# MMProtoShield.net
KiCad netlist of a schematic drawn in EAGLE
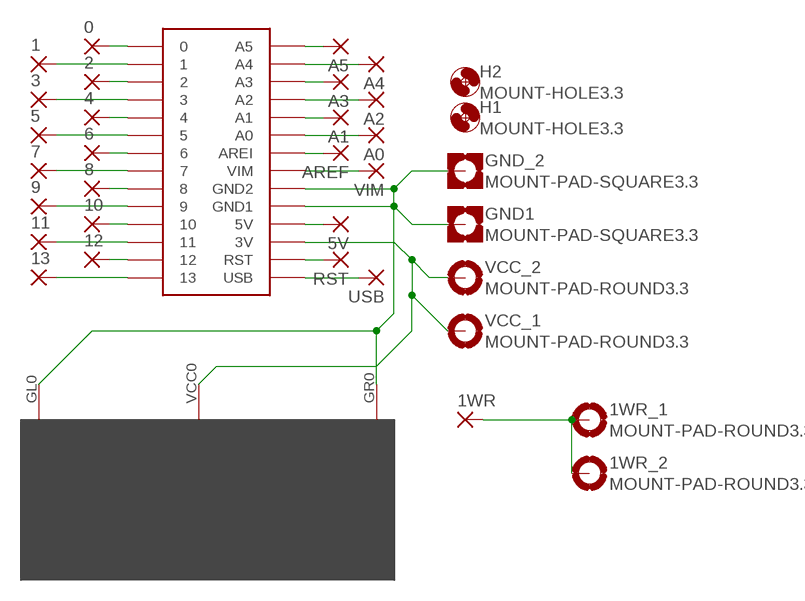
[diagram p0: schematic, sheet 1]

(export (version "E")
  (design (tool "Eeschema 10.0.6"))
  (components
    (comp (ref "0")
      (value "1,6/0,9")
      (footprint "eagle-import:1,6_0,9")
      (libsource (lib "eagle-import") (part "1,6/0,9"))
    )
    (comp (ref "1")
      (value "1,6/0,9")
      (footprint "eagle-import:1,6_0,9")
      (libsource (lib "eagle-import") (part "1,6/0,9"))
    )
    (comp (ref "1WR")
      (value "1,6/0,9")
      (footprint "eagle-import:1,6_0,9")
      (libsource (lib "eagle-import") (part "1,6/0,9"))
    )
    (comp (ref "1WR_1")
      (value "MOUNT-PAD-ROUND3.3")
      (footprint "eagle-import:3,3-PAD")
      (libsource (lib "eagle-import") (part "MOUNT-PAD-ROUND3.3"))
    )
    (comp (ref "1WR_2")
      (value "MOUNT-PAD-ROUND3.3")
      (footprint "eagle-import:3,3-PAD")
      (libsource (lib "eagle-import") (part "MOUNT-PAD-ROUND3.3"))
    )
    (comp (ref "2")
      (value "1,6/0,9")
      (footprint "eagle-import:1,6_0,9")
      (libsource (lib "eagle-import") (part "1,6/0,9"))
    )
    (comp (ref "3")
      (value "1,6/0,9")
      (footprint "eagle-import:1,6_0,9")
      (libsource (lib "eagle-import") (part "1,6/0,9"))
    )
    (comp (ref "4")
      (value "1,6/0,9")
      (footprint "eagle-import:1,6_0,9")
      (libsource (lib "eagle-import") (part "1,6/0,9"))
    )
    (comp (ref "5")
      (value "1,6/0,9")
      (footprint "eagle-import:1,6_0,9")
      (libsource (lib "eagle-import") (part "1,6/0,9"))
    )
    (comp (ref "5V")
      (value "1,6/0,9")
      (footprint "eagle-import:1,6_0,9")
      (libsource (lib "eagle-import") (part "1,6/0,9"))
    )
    (comp (ref "6")
      (value "1,6/0,9")
      (footprint "eagle-import:1,6_0,9")
      (libsource (lib "eagle-import") (part "1,6/0,9"))
    )
    (comp (ref "7")
      (value "1,6/0,9")
      (footprint "eagle-import:1,6_0,9")
      (libsource (lib "eagle-import") (part "1,6/0,9"))
    )
    (comp (ref "8")
      (value "1,6/0,9")
      (footprint "eagle-import:1,6_0,9")
      (libsource (lib "eagle-import") (part "1,6/0,9"))
    )
    (comp (ref "9")
      (value "1,6/0,9")
      (footprint "eagle-import:1,6_0,9")
      (libsource (lib "eagle-import") (part "1,6/0,9"))
    )
    (comp (ref "10")
      (value "1,6/0,9")
      (footprint "eagle-import:1,6_0,9")
      (libsource (lib "eagle-import") (part "1,6/0,9"))
    )
    (comp (ref "11")
      (value "1,6/0,9")
      (footprint "eagle-import:1,6_0,9")
      (libsource (lib "eagle-import") (part "1,6/0,9"))
    )
    (comp (ref "12")
      (value "1,6/0,9")
      (footprint "eagle-import:1,6_0,9")
      (libsource (lib "eagle-import") (part "1,6/0,9"))
    )
    (comp (ref "13")
      (value "1,6/0,9")
      (footprint "eagle-import:1,6_0,9")
      (libsource (lib "eagle-import") (part "1,6/0,9"))
    )
    (comp (ref "A0")
      (value "1,6/0,9")
      (footprint "eagle-import:1,6_0,9")
      (libsource (lib "eagle-import") (part "1,6/0,9"))
    )
    (comp (ref "A1")
      (value "1,6/0,9")
      (footprint "eagle-import:1,6_0,9")
      (libsource (lib "eagle-import") (part "1,6/0,9"))
    )
    (comp (ref "A2")
      (value "1,6/0,9")
      (footprint "eagle-import:1,6_0,9")
      (libsource (lib "eagle-import") (part "1,6/0,9"))
    )
    (comp (ref "A3")
      (value "1,6/0,9")
      (footprint "eagle-import:1,6_0,9")
      (libsource (lib "eagle-import") (part "1,6/0,9"))
    )
    (comp (ref "A4")
      (value "1,6/0,9")
      (footprint "eagle-import:1,6_0,9")
      (libsource (lib "eagle-import") (part "1,6/0,9"))
    )
    (comp (ref "A5")
      (value "1,6/0,9")
      (footprint "eagle-import:1,6_0,9")
      (libsource (lib "eagle-import") (part "1,6/0,9"))
    )
    (comp (ref "AREF")
      (value "1,6/0,9")
      (footprint "eagle-import:1,6_0,9")
      (libsource (lib "eagle-import") (part "1,6/0,9"))
    )
    (comp (ref "GND1")
      (value "MOUNT-PAD-SQUARE3.3")
      (footprint "eagle-import:3,3-PAD-SQUARE")
      (libsource (lib "eagle-import") (part "MOUNT-PAD-SQUARE3.3"))
    )
    (comp (ref "GND_2")
      (value "MOUNT-PAD-SQUARE3.3")
      (footprint "eagle-import:3,3-PAD-SQUARE")
      (libsource (lib "eagle-import") (part "MOUNT-PAD-SQUARE3.3"))
    )
    (comp (ref "H1")
      (value "MOUNT-HOLE3.3")
      (footprint "eagle-import:3,3")
      (libsource (lib "eagle-import") (part "MOUNT-HOLE3.3"))
    )
    (comp (ref "H2")
      (value "MOUNT-HOLE3.3")
      (footprint "eagle-import:3,3")
      (libsource (lib "eagle-import") (part "MOUNT-HOLE3.3"))
    )
    (comp (ref "RST")
      (value "1,6/0,9")
      (footprint "eagle-import:1,6_0,9")
      (libsource (lib "eagle-import") (part "1,6/0,9"))
    )
    (comp (ref "U$1")
      (value "METRO_MINI_FOOTPRINT")
      (footprint "eagle-import:METRO_MINI_FOOTPRINT")
      (libsource (lib "eagle-import") (part "METRO_MINI_FOOTPRINT"))
    )
    (comp (ref "U$2")
      (value "PROTOAREA")
      (footprint "eagle-import:PROTOAREA")
      (libsource (lib "eagle-import") (part "PROTOAREA"))
    )
    (comp (ref "USB")
      (value "1,6/0,9")
      (footprint "eagle-import:1,6_0,9")
      (libsource (lib "eagle-import") (part "1,6/0,9"))
    )
    (comp (ref "VCC_1")
      (value "MOUNT-PAD-ROUND3.3")
      (footprint "eagle-import:3,3-PAD")
      (libsource (lib "eagle-import") (part "MOUNT-PAD-ROUND3.3"))
    )
    (comp (ref "VCC_2")
      (value "MOUNT-PAD-ROUND3.3")
      (footprint "eagle-import:3,3-PAD")
      (libsource (lib "eagle-import") (part "MOUNT-PAD-ROUND3.3"))
    )
    (comp (ref "VIM")
      (value "1,6/0,9")
      (footprint "eagle-import:1,6_0,9")
      (libsource (lib "eagle-import") (part "1,6/0,9"))
    )
  )
  (nets
    (net (code "1") (name "Net-(0-P)") (class "Default")
      (node (ref "0") (pin "1") (pinfunction "P_1") (pintype "passive"))
      (node (ref "U$1") (pin "0") (pinfunction "0_0") (pintype "bidirectional"))
    )
    (net (code "2") (name "Net-(1-P)") (class "Default")
      (node (ref "1") (pin "1") (pinfunction "P_1") (pintype "passive"))
      (node (ref "U$1") (pin "1") (pinfunction "1_1") (pintype "bidirectional"))
    )
    (net (code "3") (name "Net-(1WR-P)") (class "Default")
      (node (ref "1WR") (pin "1") (pinfunction "P_1") (pintype "passive"))
      (node (ref "1WR_1") (pin "B3,3") (pinfunction "MOUNT_B3,3") (pintype "passive"))
      (node (ref "1WR_2") (pin "B3,3") (pinfunction "MOUNT_B3,3") (pintype "passive"))
    )
    (net (code "4") (name "Net-(2-P)") (class "Default")
      (node (ref "2") (pin "1") (pinfunction "P_1") (pintype "passive"))
      (node (ref "U$1") (pin "2") (pinfunction "2_2") (pintype "bidirectional"))
    )
    (net (code "5") (name "Net-(3-P)") (class "Default")
      (node (ref "3") (pin "1") (pinfunction "P_1") (pintype "passive"))
      (node (ref "U$1") (pin "3") (pinfunction "3_3") (pintype "bidirectional"))
    )
    (net (code "6") (name "Net-(4-P)") (class "Default")
      (node (ref "4") (pin "1") (pinfunction "P_1") (pintype "passive"))
      (node (ref "U$1") (pin "4") (pinfunction "4_4") (pintype "bidirectional"))
    )
    (net (code "7") (name "Net-(5-P)") (class "Default")
      (node (ref "5") (pin "1") (pinfunction "P_1") (pintype "passive"))
      (node (ref "U$1") (pin "5") (pinfunction "5_5") (pintype "bidirectional"))
    )
    (net (code "8") (name "Net-(5V-P)") (class "Default")
      (node (ref "5V") (pin "1") (pinfunction "P_1") (pintype "passive"))
      (node (ref "U$1") (pin "5V") (pinfunction "5V_5V") (pintype "bidirectional"))
    )
    (net (code "9") (name "Net-(6-P)") (class "Default")
      (node (ref "6") (pin "1") (pinfunction "P_1") (pintype "passive"))
      (node (ref "U$1") (pin "6") (pinfunction "6_6") (pintype "bidirectional"))
    )
    (net (code "10") (name "Net-(7-P)") (class "Default")
      (node (ref "7") (pin "1") (pinfunction "P_1") (pintype "passive"))
      (node (ref "U$1") (pin "7") (pinfunction "7_7") (pintype "bidirectional"))
    )
    (net (code "11") (name "Net-(8-P)") (class "Default")
      (node (ref "8") (pin "1") (pinfunction "P_1") (pintype "passive"))
      (node (ref "U$1") (pin "8") (pinfunction "8_8") (pintype "bidirectional"))
    )
    (net (code "12") (name "Net-(9-P)") (class "Default")
      (node (ref "9") (pin "1") (pinfunction "P_1") (pintype "passive"))
      (node (ref "U$1") (pin "9") (pinfunction "9_9") (pintype "bidirectional"))
    )
    (net (code "13") (name "Net-(10-P)") (class "Default")
      (node (ref "10") (pin "1") (pinfunction "P_1") (pintype "passive"))
      (node (ref "U$1") (pin "10") (pinfunction "10_10") (pintype "bidirectional"))
    )
    (net (code "14") (name "Net-(11-P)") (class "Default")
      (node (ref "11") (pin "1") (pinfunction "P_1") (pintype "passive"))
      (node (ref "U$1") (pin "11") (pinfunction "11_11") (pintype "bidirectional"))
    )
    (net (code "15") (name "Net-(12-P)") (class "Default")
      (node (ref "12") (pin "1") (pinfunction "P_1") (pintype "passive"))
      (node (ref "U$1") (pin "12") (pinfunction "12_12") (pintype "bidirectional"))
    )
    (net (code "16") (name "Net-(13-P)") (class "Default")
      (node (ref "13") (pin "1") (pinfunction "P_1") (pintype "passive"))
      (node (ref "U$1") (pin "13") (pinfunction "13_13") (pintype "bidirectional"))
    )
    (net (code "17") (name "Net-(A0-P)") (class "Default")
      (node (ref "A0") (pin "1") (pinfunction "P_1") (pintype "passive"))
      (node (ref "U$1") (pin "A0") (pinfunction "A0_A0") (pintype "bidirectional"))
    )
    (net (code "18") (name "Net-(A1-P)") (class "Default")
      (node (ref "A1") (pin "1") (pinfunction "P_1") (pintype "passive"))
      (node (ref "U$1") (pin "A1") (pinfunction "A1_A1") (pintype "bidirectional"))
    )
    (net (code "19") (name "Net-(A2-P)") (class "Default")
      (node (ref "A2") (pin "1") (pinfunction "P_1") (pintype "passive"))
      (node (ref "U$1") (pin "A2") (pinfunction "A2_A2") (pintype "bidirectional"))
    )
    (net (code "20") (name "Net-(A3-P)") (class "Default")
      (node (ref "A3") (pin "1") (pinfunction "P_1") (pintype "passive"))
      (node (ref "U$1") (pin "A3") (pinfunction "A3_A3") (pintype "bidirectional"))
    )
    (net (code "21") (name "Net-(A4-P)") (class "Default")
      (node (ref "A4") (pin "1") (pinfunction "P_1") (pintype "passive"))
      (node (ref "U$1") (pin "A4") (pinfunction "A4_A4") (pintype "bidirectional"))
    )
    (net (code "22") (name "Net-(A5-P)") (class "Default")
      (node (ref "A5") (pin "1") (pinfunction "P_1") (pintype "passive"))
      (node (ref "U$1") (pin "A5") (pinfunction "A5_A5") (pintype "bidirectional"))
    )
    (net (code "23") (name "Net-(AREF-P)") (class "Default")
      (node (ref "AREF") (pin "1") (pinfunction "P_1") (pintype "passive"))
      (node (ref "U$1") (pin "AREF") (pinfunction "AREI_AREF") (pintype "bidirectional"))
    )
    (net (code "24") (name "Net-(GND1-MOUNT)") (class "Default")
      (node (ref "GND1") (pin "B3,3") (pinfunction "MOUNT_B3,3") (pintype "passive"))
      (node (ref "GND_2") (pin "B3,3") (pinfunction "MOUNT_B3,3") (pintype "passive"))
      (node (ref "U$1") (pin "GND1") (pinfunction "GND1_GND1") (pintype "bidirectional"))
      (node (ref "U$1") (pin "GND2") (pinfunction "GND2_GND2") (pintype "bidirectional"))
      (node (ref "U$2") (pin "GL0") (pinfunction "RAIL1_GL0") (pintype "bidirectional"))
      (node (ref "U$2") (pin "GR0") (pinfunction "RAIL3_GR0") (pintype "bidirectional"))
    )
    (net (code "25") (name "Net-(RST-P)") (class "Default")
      (node (ref "RST") (pin "1") (pinfunction "P_1") (pintype "passive"))
      (node (ref "U$1") (pin "RST") (pinfunction "RST_RST") (pintype "bidirectional"))
    )
    (net (code "26") (name "Net-(U$1-VIM)") (class "Default")
      (node (ref "U$1") (pin "VIN") (pinfunction "VIM_VIN") (pintype "bidirectional"))
      (node (ref "VIM") (pin "1") (pinfunction "P_1") (pintype "passive"))
    )
    (net (code "27") (name "Net-(U$2-RAIL2)") (class "Default")
      (node (ref "U$1") (pin "3V") (pinfunction "3V_3V") (pintype "bidirectional"))
      (node (ref "U$2") (pin "VCC0") (pinfunction "RAIL2_VCC0") (pintype "bidirectional"))
      (node (ref "VCC_1") (pin "B3,3") (pinfunction "MOUNT_B3,3") (pintype "passive"))
      (node (ref "VCC_2") (pin "B3,3") (pinfunction "MOUNT_B3,3") (pintype "passive"))
    )
    (net (code "28") (name "Net-(USB-P)") (class "Default")
      (node (ref "U$1") (pin "USB") (pinfunction "USB_USB") (pintype "bidirectional"))
      (node (ref "USB") (pin "1") (pinfunction "P_1") (pintype "passive"))
    )
  )
)
